# FRONT-UNIT-7INCH.net
KiCad netlist of a schematic drawn in Altium Designer
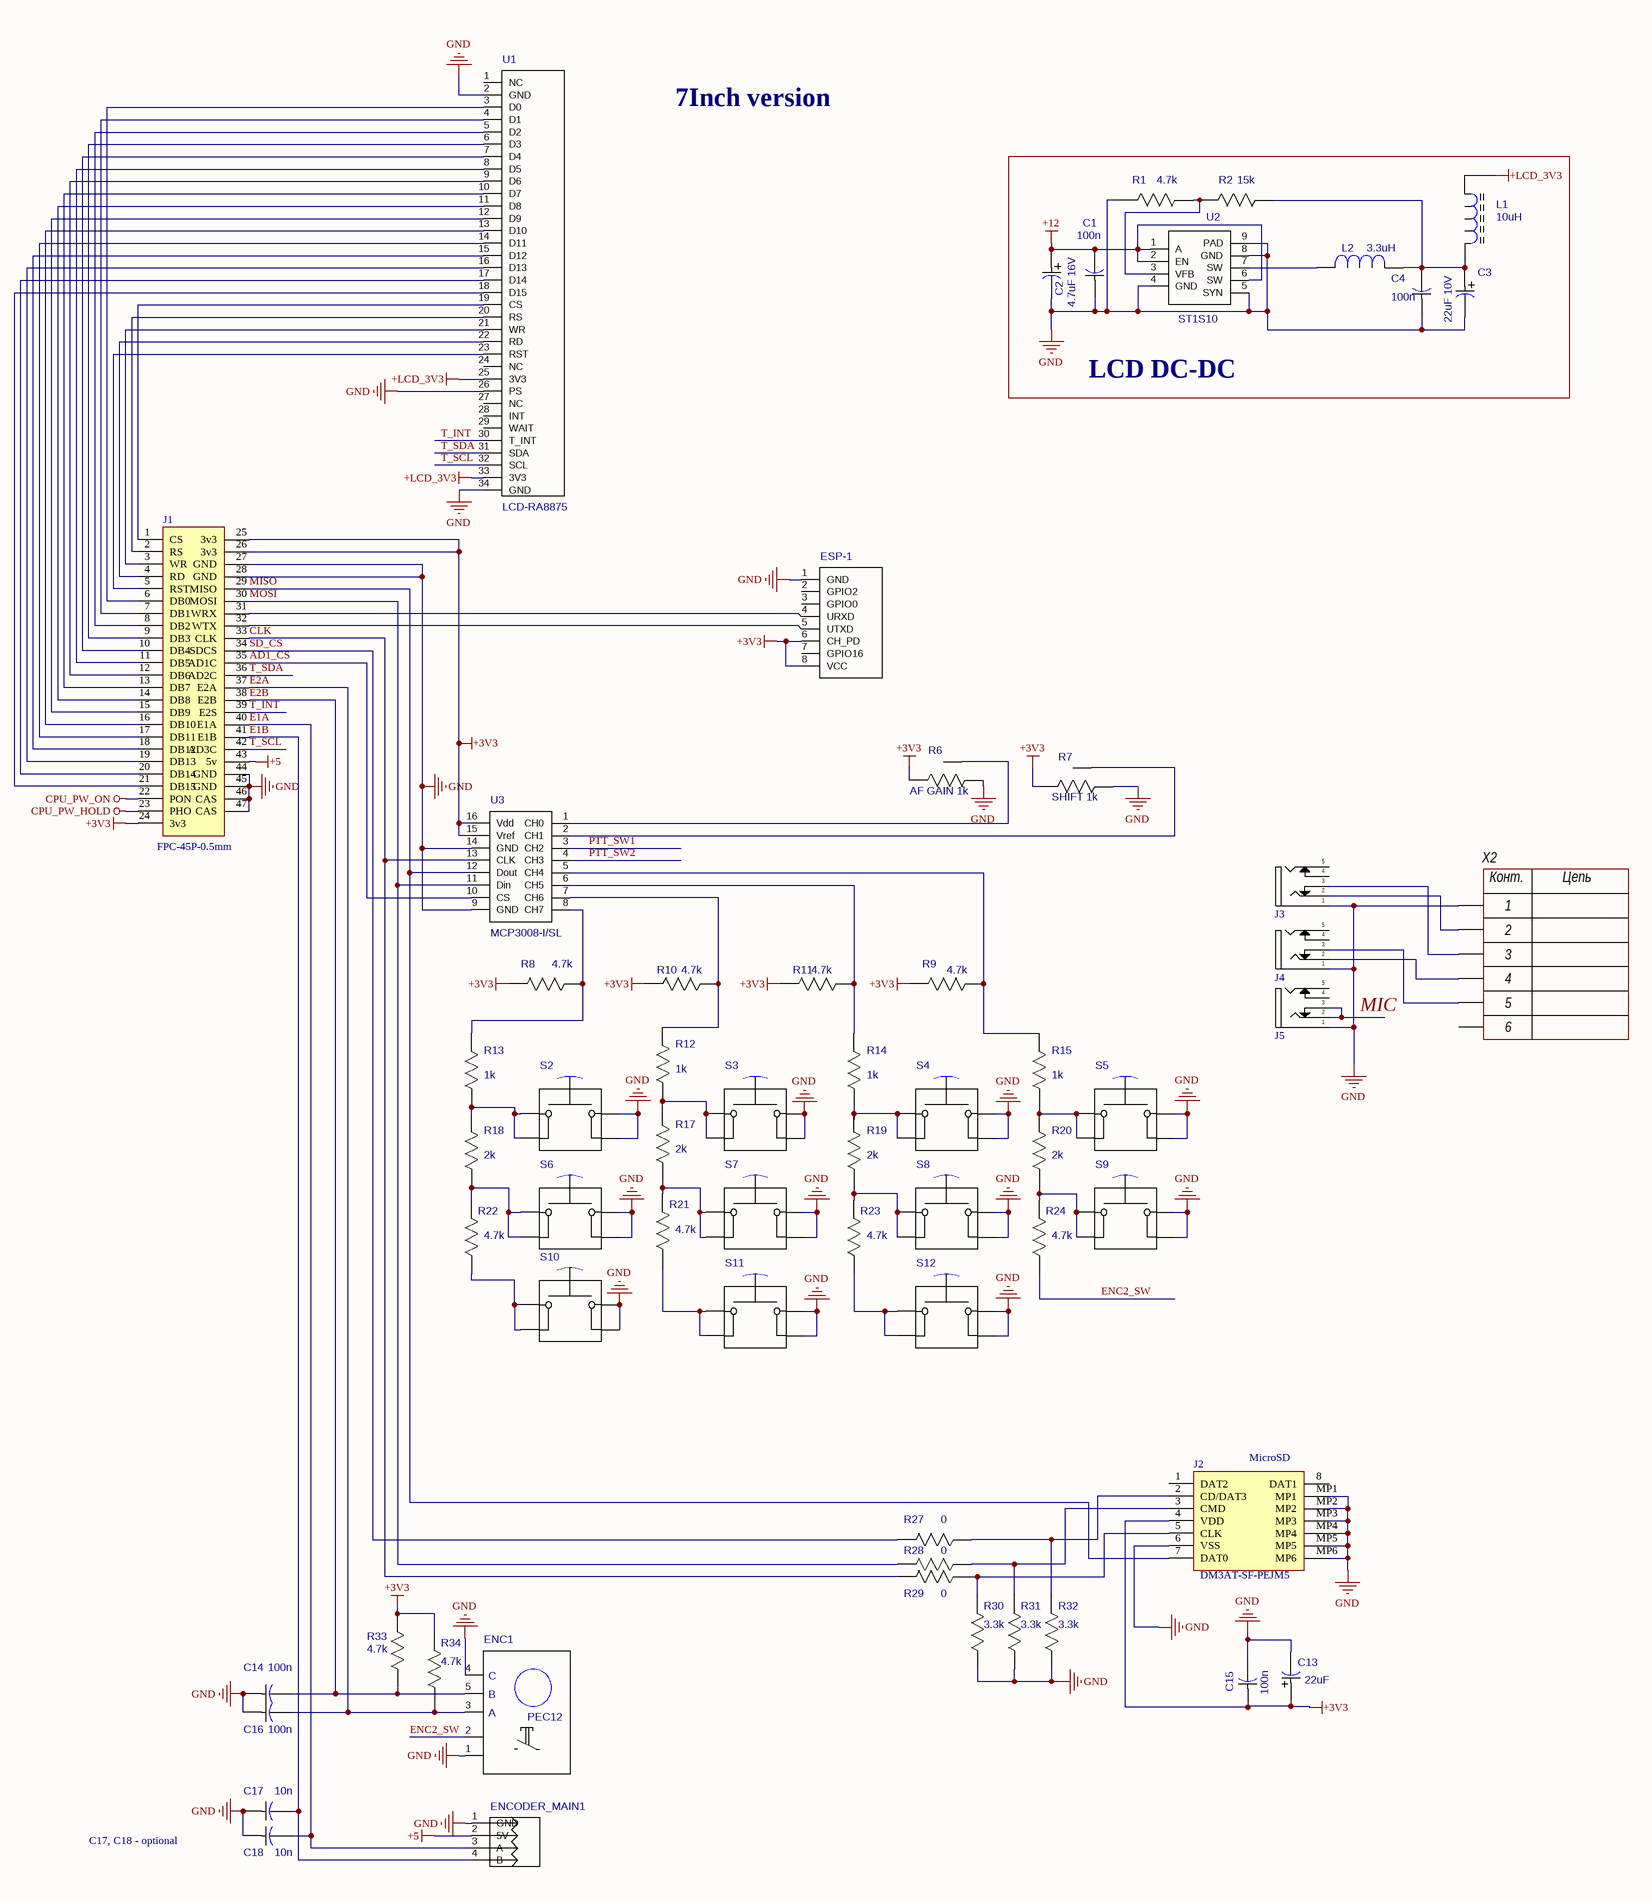
[diagram p0: FRONT-UNIT-7INCH.SCHDOC, left]
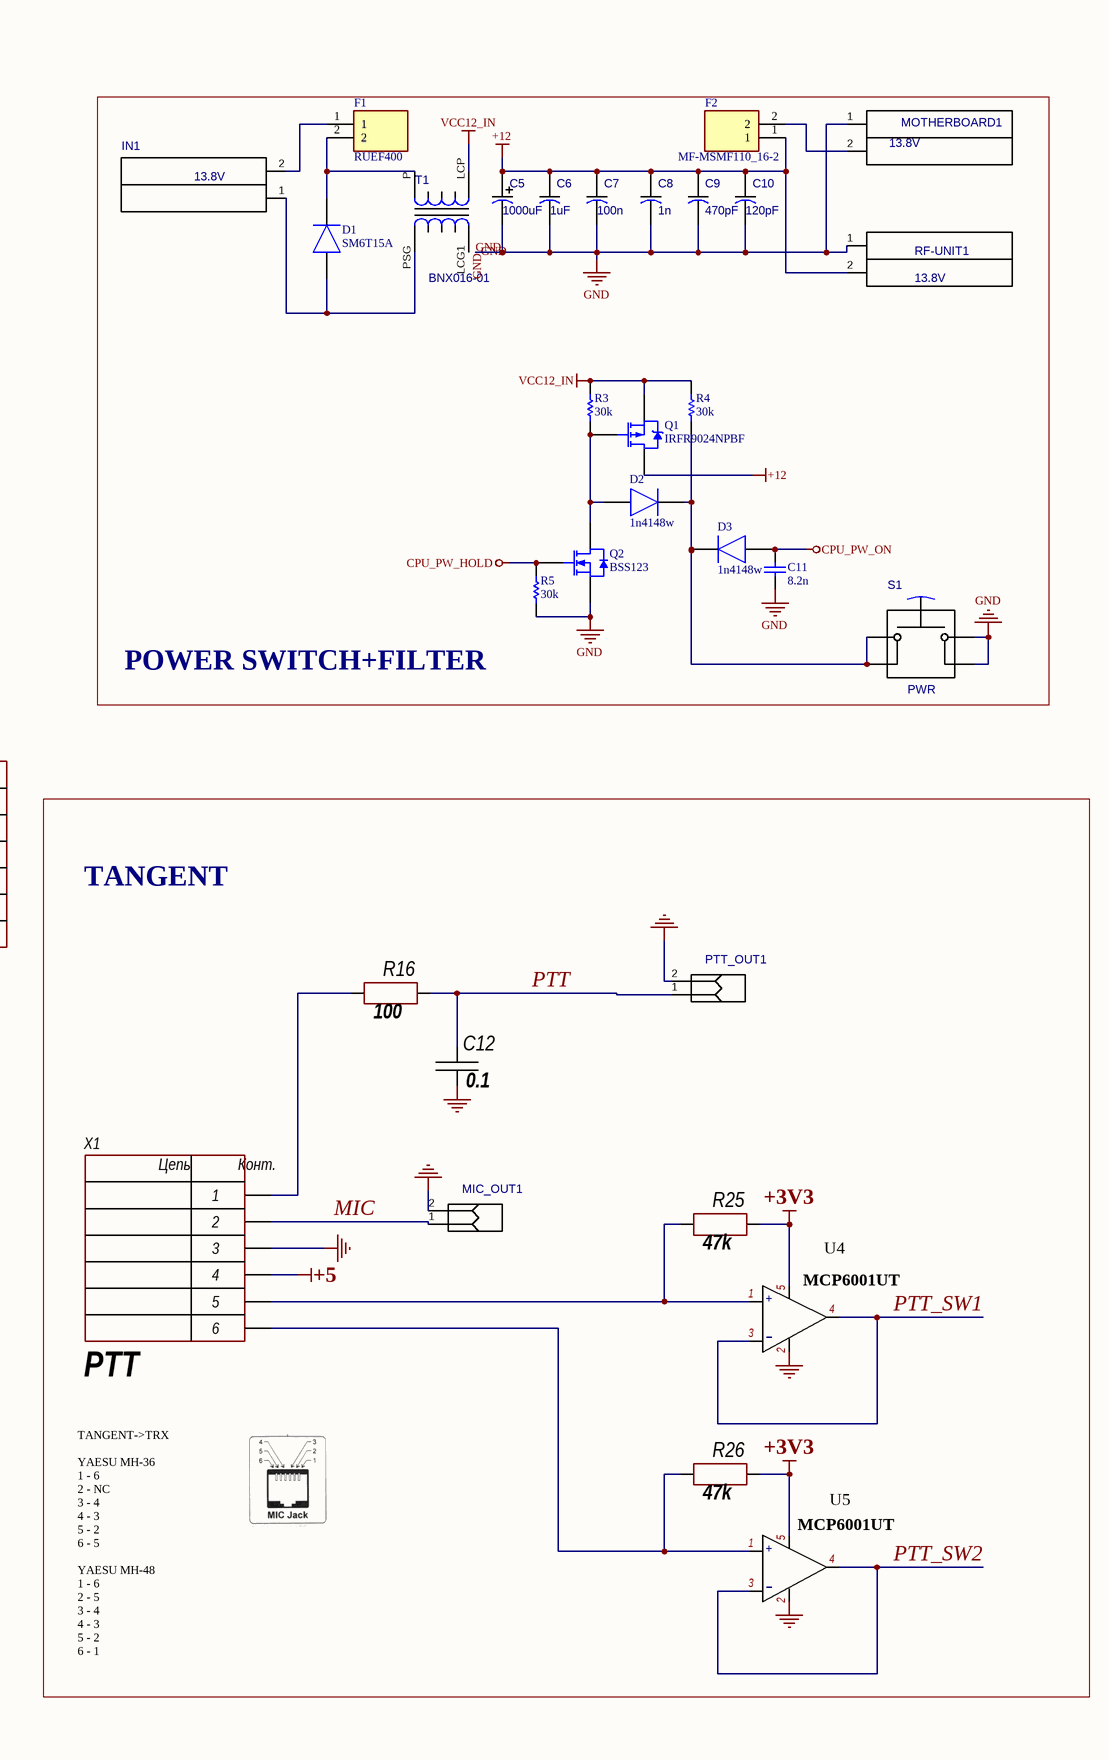
[diagram p1: FRONT-UNIT-7INCH.SCHDOC, right]

(export (version "E")
  (design (tool "Eeschema 10.0.6"))
  (components
    (comp (ref "C1")
      (value "100n")
      (footprint "CAP_0805")
      (description "CAP_0805")
      (libsource (lib "*") (part "CAP_0805"))
    )
    (comp (ref "C2")
      (value "4.7uF 16V")
      (footprint "CAPAE-6.6x6.6h5.4")
      (description "CAPAE_6.6x6.6h5.4")
      (libsource (lib "*") (part "CAPAE_6.6x6.6h5.4"))
    )
    (comp (ref "C3")
      (value "22uF 10V")
      (footprint "TC_1411")
      (description "CAPAE_4.3x4.3h5.4")
      (libsource (lib "*") (part "CAPAE_4.3x4.3h5.4"))
    )
    (comp (ref "C4")
      (value "100n")
      (footprint "CAP_0805")
      (description "CAP_0805")
      (libsource (lib "FRONT-UNIT-7INCH") (part "CAP_0805"))
    )
    (comp (ref "C5")
      (value "1000uF")
      (footprint "CAPPR-6.35/8.9")
      (description "CAP250RP")
      (libsource (lib "*") (part "CAP250RP"))
    )
    (comp (ref "C6")
      (value "1uF")
      (footprint "CAP_1206")
      (description "CAP_1206")
      (libsource (lib "*") (part "CAP_1206"))
    )
    (comp (ref "C7")
      (value "100n")
      (footprint "CAP_1206")
      (description "CAP_1206")
      (libsource (lib "*") (part "CAP_1206"))
    )
    (comp (ref "C8")
      (value "1n")
      (footprint "CAP_1206")
      (description "CAP_1206")
      (libsource (lib "*") (part "CAP_1206"))
    )
    (comp (ref "C9")
      (value "470pF")
      (footprint "CAP_1206")
      (description "CAP_1206")
      (libsource (lib "*") (part "CAP_1206"))
    )
    (comp (ref "C10")
      (value "120pF")
      (footprint "CAP_1206")
      (description "CAP_1206")
      (libsource (lib "FRONT-UNIT-7INCH") (part "CAP_1206"))
    )
    (comp (ref "C11")
      (value "8.2n")
      (footprint "CAPC2013X94X50LL20T25")
      (description "CAP_1206")
      (fields
        (field (name "MANUFACTURER") "AVX Interconnect / Elco")
        (field (name "PART NUMBER") "08055C822KAT2A")
      )
      (libsource (lib "Altium Content Vault") (part "CAP"))
    )
    (comp (ref "C12")
      (value "0.1")
      (footprint "CH0805C")
      (libsource (lib "FRONT-UNIT-7INCH") (part "Capacitor"))
    )
    (comp (ref "C13")
      (value "22uF")
      (footprint "TC_1411")
      (description "EEEFC_sizeB")
      (libsource (lib "*") (part "EEEFC_sizeB"))
    )
    (comp (ref "C14")
      (value "100n")
      (footprint "CAP_0805")
      (description "CAP_0805")
      (libsource (lib "*") (part "CAP_0805"))
    )
    (comp (ref "C15")
      (value "100n")
      (footprint "CAP_0805")
      (description "CAP_0805")
      (libsource (lib "*") (part "CAP_0805"))
    )
    (comp (ref "C16")
      (value "100n")
      (footprint "CAP_0805")
      (description "CAP_0805")
      (libsource (lib "*") (part "CAP_0805"))
    )
    (comp (ref "C17")
      (value "10n")
      (footprint "CAP_0805")
      (description "CAP_0805")
      (libsource (lib "*") (part "CAP_0805"))
    )
    (comp (ref "C18")
      (value "10n")
      (footprint "CAP_0805")
      (description "CAP_0805")
      (libsource (lib "*") (part "CAP_0805"))
    )
    (comp (ref "D1")
      (value "SM6T15A")
      (footprint "SamacSys:SMBJ36CATR")
      (description "Diode")
      (fields (field (name "MOUSER PART NUMBER") "511-SM6T15A") (field (name "RS PART NUMBER") "4864915P"))
      (libsource (lib "*") (part "SM6T15A"))
    )
    (comp (ref "D2")
      (value "1n4148w")
      (footprint "SamacSys:SOD3716X135N")
      (description "Diode")
      (libsource (lib "*") (part "1n4148w"))
    )
    (comp (ref "D3")
      (value "1n4148w")
      (footprint "SamacSys:SOD3716X135N")
      (description "Diode")
      (libsource (lib "*") (part "1n4148w"))
    )
    (comp (ref "ENC1") (value "PEC12") (footprint "PEC12") (libsource (lib "*") (part "PEC12")))
    (comp (ref "ENCODER_MAIN1")
      (value "OPTICAL ENCODER")
      (footprint "644456-4")
      (libsource (lib "*") (part "644456-4"))
    )
    (comp (ref "ESP-1")
      (value "ESP-01 ESP8266")
      (footprint "ESP-01 ESP8266")
      (libsource (lib "*") (part "ESP-01 ESP8266"))
    )
    (comp (ref "F1")
      (value "RUEF400")
      (footprint "SamacSys:RUEF400")
      (description "Fuse")
      (fields (field (name "MOUSER PART NUMBER") "650-RUEF400") (field (name "RS PART NUMBER") "5176837P"))
      (libsource (lib "*") (part "RUEF400"))
    )
    (comp (ref "F2")
      (value "MF-MSMF110_16-2")
      (footprint "SamacSys:FUSC4632X85N")
      (description "Fuse")
      (fields
        (field (name "MANUFACTURER_PART_NUMBER") "MF-MSMF110/16-2")
        (field (name "MOUSER PART NUMBER") "652-MF-MSMF110/16-2")
      )
      (libsource (lib "*") (part "MF-MSMF110_16-2"))
    )
    (comp (ref "IN1")
      (value "13.8V")
      (footprint "JX2")
      (description "JX2")
      (libsource (lib "*") (part "JX2"))
    )
    (comp (ref "J1")
      (value "FPC-45P-0.5mm")
      (footprint "FH12S45S05SH60")
      (description "Connector")
      (fields
        (field (name "MANUFACTURER_PART_NUMBER") "FH12S-45S-0.5SH(55)")
        (field (name "MOUSER PART NUMBER") "798-FH12S-45S-05SH55")
      )
      (libsource (lib "*") (part "FH12S-45S-0.5SH_55_"))
    )
    (comp (ref "J2")
      (value "DM3AT-SF-PEJM5")
      (footprint "SamacSys:DM3ATSFPEJM5")
      (description "Connector")
      (libsource (lib "*") (part "DM3AT-SF-PEJM5"))
    )
    (comp (ref "J3") (value "PJ-3,5") (footprint "Audio-PJ-392") (libsource (lib "SDR_ham") (part "PJ-3,5")))
    (comp (ref "J4") (value "PJ-3,5") (footprint "Audio-PJ-392") (libsource (lib "SDR_ham") (part "PJ-3,5")))
    (comp (ref "J5") (value "PJ-3,5") (footprint "Audio-PJ-392") (libsource (lib "SDR_ham") (part "PJ-3,5")))
    (comp (ref "L1")
      (value "10uH")
      (footprint "B82464Z4")
      (description "Inductor")
      (libsource (lib "FRONT-UNIT-7INCH") (part "IND_FERRITE_CORE"))
    )
    (comp (ref "L2")
      (value "3.3uH")
      (footprint "IND_1812")
      (description "IND_1812")
      (libsource (lib "*") (part "IND_1812"))
    )
    (comp (ref "MIC_OUT1")
      (value "MIC_OUT")
      (footprint "51022-0200")
      (description "51022-0200")
      (libsource (lib "*") (part "51022-0200"))
    )
    (comp (ref "MOTHERBOARD1")
      (value "13.8V")
      (footprint "JX2")
      (description "JX2")
      (libsource (lib "*") (part "JX2"))
    )
    (comp (ref "PTT_OUT1")
      (value "PTT_OUT")
      (footprint "51022-0200")
      (description "51022-0200")
      (libsource (lib "*") (part "51022-0200"))
    )
    (comp (ref "Q1")
      (value "IRFR9024NPBF")
      (footprint "ONSC-DPAK-3-369C-01_V")
      (description "IRFR9024NPBF, Транзистор, Р-канал 55В 11А")
      (fields (field (name "MANUFACTURER") "On Semiconductor") (field (name "PARTNUMBER") "NTD2955G"))
      (libsource (lib "Altium Content Vault") (part "ONSC-PMOS-G1S3D4-3_B"))
    )
    (comp (ref "Q2")
      (value "BSS123")
      (footprint "FAIR-SOT23-3_V")
      (fields (field (name "MANUFACTURER") "Fairchild"))
      (libsource (lib "Altium Content Vault") (part "NEMOS-GSD-3"))
    )
    (comp (ref "R1")
      (value "4.7k")
      (footprint "RES_0805")
      (description "RES_0805")
      (libsource (lib "") (part "RES_0805_1"))
    )
    (comp (ref "R2")
      (value "15k")
      (footprint "RES_0805")
      (description "RES_0805")
      (fields (field (name "Comment") "120k+100k"))
      (libsource (lib "") (part "RES_0805_1"))
    )
    (comp (ref "R3")
      (value "30k")
      (footprint "RESC2013X60X40NL20T25")
      (description "RES_0805")
      (fields (field (name "MANUFACTURER") "Panasonic") (field (name "PART NUMBER") "ERA-6AEB303V"))
      (libsource (lib "Altium Content Vault") (part "RES"))
    )
    (comp (ref "R4")
      (value "30k")
      (footprint "RESC2013X60X40NL20T25")
      (description "RES_0805")
      (fields (field (name "MANUFACTURER") "Panasonic") (field (name "PART NUMBER") "ERA-6AEB303V"))
      (libsource (lib "Altium Content Vault") (part "RES"))
    )
    (comp (ref "R5")
      (value "30k")
      (footprint "RESC2013X60X40NL20T25")
      (description "RES_0805")
      (fields (field (name "MANUFACTURER") "Panasonic") (field (name "PART NUMBER") "ERA-6AEB303V"))
      (libsource (lib "Altium Content Vault") (part "RES"))
    )
    (comp (ref "R6")
      (value "AF GAIN 1k")
      (footprint "PTV09")
      (description "Adjustable Resistor PTV09")
      (fields (field (name "Comment") "ptv09a-4225f-b102"))
      (libsource (lib "*") (part "PTV09"))
    )
    (comp (ref "R7")
      (value "SHIFT 1k")
      (footprint "PTV09")
      (description "Adjustable Resistor PTV09")
      (fields (field (name "Comment") "ptv09a-4225f-b102"))
      (libsource (lib "*") (part "PTV09"))
    )
    (comp (ref "R8")
      (value "4.7k")
      (footprint "RES_0805")
      (description "RES_0805")
      (libsource (lib "*") (part "RES_0805"))
    )
    (comp (ref "R9")
      (value "4.7k")
      (footprint "RES_0805")
      (description "RES_0805")
      (libsource (lib "*") (part "RES_0805"))
    )
    (comp (ref "R10")
      (value "4.7k")
      (footprint "RES_0805")
      (description "RES_0805")
      (libsource (lib "*") (part "RES_0805"))
    )
    (comp (ref "R11")
      (value "4.7k")
      (footprint "RES_0805")
      (description "RES_0805")
      (libsource (lib "*") (part "RES_0805"))
    )
    (comp (ref "R12")
      (value "1k")
      (footprint "RES_0805")
      (description "RES_0805")
      (libsource (lib "*") (part "RES_0805"))
    )
    (comp (ref "R13")
      (value "1k")
      (footprint "RES_0805")
      (description "RES_0805")
      (libsource (lib "*") (part "RES_0805"))
    )
    (comp (ref "R14")
      (value "1k")
      (footprint "RES_0805")
      (description "RES_0805")
      (libsource (lib "*") (part "RES_0805"))
    )
    (comp (ref "R15")
      (value "1k")
      (footprint "RES_0805")
      (description "RES_0805")
      (libsource (lib "*") (part "RES_0805"))
    )
    (comp (ref "R16")
      (value "100")
      (footprint "FRONT-UNIT-7INCH:CH0805R")
      (libsource (lib "Discrete") (part "Resistor"))
    )
    (comp (ref "R17")
      (value "2k")
      (footprint "RES_0805")
      (description "RES_0805")
      (libsource (lib "*") (part "RES_0805"))
    )
    (comp (ref "R18")
      (value "2k")
      (footprint "RES_0805")
      (description "RES_0805")
      (libsource (lib "*") (part "RES_0805"))
    )
    (comp (ref "R19")
      (value "2k")
      (footprint "RES_0805")
      (description "RES_0805")
      (libsource (lib "*") (part "RES_0805"))
    )
    (comp (ref "R20")
      (value "2k")
      (footprint "RES_0805")
      (description "RES_0805")
      (libsource (lib "*") (part "RES_0805"))
    )
    (comp (ref "R21")
      (value "4.7k")
      (footprint "RES_0805")
      (description "RES_0805")
      (libsource (lib "*") (part "RES_0805"))
    )
    (comp (ref "R22")
      (value "4.7k")
      (footprint "RES_0805")
      (description "RES_0805")
      (libsource (lib "*") (part "RES_0805"))
    )
    (comp (ref "R23")
      (value "4.7k")
      (footprint "RES_0805")
      (description "RES_0805")
      (libsource (lib "*") (part "RES_0805"))
    )
    (comp (ref "R24")
      (value "4.7k")
      (footprint "RES_0805")
      (description "RES_0805")
      (libsource (lib "*") (part "RES_0805"))
    )
    (comp (ref "R25")
      (value "47k")
      (footprint "FRONT-UNIT-7INCH:CH0805R")
      (libsource (lib "Discrete") (part "Resistor"))
    )
    (comp (ref "R26")
      (value "47k")
      (footprint "FRONT-UNIT-7INCH:CH0805C")
      (libsource (lib "Discrete") (part "Resistor"))
    )
    (comp (ref "R27")
      (value "0")
      (footprint "RES_0805")
      (description "RES_0805")
      (libsource (lib "*") (part "RES_0805"))
    )
    (comp (ref "R28")
      (value "0")
      (footprint "RES_0805")
      (description "RES_0805")
      (libsource (lib "*") (part "RES_0805"))
    )
    (comp (ref "R29")
      (value "0")
      (footprint "RES_0805")
      (description "RES_0805")
      (libsource (lib "*") (part "RES_0805"))
    )
    (comp (ref "R30")
      (value "3.3k")
      (footprint "RES_0805")
      (description "RES_0805")
      (libsource (lib "*") (part "RES_0805"))
    )
    (comp (ref "R31")
      (value "3.3k")
      (footprint "RES_0805")
      (description "RES_0805")
      (libsource (lib "*") (part "RES_0805"))
    )
    (comp (ref "R32")
      (value "3.3k")
      (footprint "RES_0805")
      (description "RES_0805")
      (libsource (lib "*") (part "RES_0805"))
    )
    (comp (ref "R33")
      (value "4.7k")
      (footprint "RES_0805")
      (description "RES_0805")
      (libsource (lib "*") (part "RES_0805"))
    )
    (comp (ref "R34")
      (value "4.7k")
      (footprint "RES_0805")
      (description "RES_0805")
      (libsource (lib "*") (part "RES_0805"))
    )
    (comp (ref "RF-UNIT1")
      (value "13.8V")
      (footprint "JX2")
      (description "JX2")
      (libsource (lib "*") (part "JX2"))
    )
    (comp (ref "S1")
      (value "PWR")
      (footprint "PTS-6-S")
      (description "PTS645SK50LFS")
      (libsource (lib "*") (part "PTS645SK50LFS"))
    )
    (comp (ref "S2")
      (value "PTS645SK50LFS")
      (footprint "PTS-6-S")
      (fields (field (name "LCSC PART #") "test"))
      (libsource (lib "*") (part "PTS645SK50LFS"))
    )
    (comp (ref "S3")
      (value "PTS645SK50LFS")
      (footprint "PTS-6-S")
      (libsource (lib "*") (part "PTS645SK50LFS"))
    )
    (comp (ref "S4")
      (value "PTS645SK50LFS")
      (footprint "PTS-6-S")
      (libsource (lib "*") (part "PTS645SK50LFS"))
    )
    (comp (ref "S5")
      (value "PTS645SK50LFS")
      (footprint "PTS-6-S")
      (libsource (lib "*") (part "PTS645SK50LFS"))
    )
    (comp (ref "S6")
      (value "PTS645SK50LFS")
      (footprint "PTS-6-S")
      (libsource (lib "*") (part "PTS645SK50LFS"))
    )
    (comp (ref "S7")
      (value "PTS645SK50LFS")
      (footprint "PTS-6-S")
      (libsource (lib "*") (part "PTS645SK50LFS"))
    )
    (comp (ref "S8")
      (value "PTS645SK50LFS")
      (footprint "PTS-6-S")
      (libsource (lib "*") (part "PTS645SK50LFS"))
    )
    (comp (ref "S9")
      (value "PTS645SK50LFS")
      (footprint "PTS-6-S")
      (libsource (lib "*") (part "PTS645SK50LFS"))
    )
    (comp (ref "S10")
      (value "PTS645SK50LFS")
      (footprint "PTS-6-S")
      (libsource (lib "*") (part "PTS645SK50LFS"))
    )
    (comp (ref "S11")
      (value "PTS645SK50LFS")
      (footprint "PTS-6-S")
      (libsource (lib "*") (part "PTS645SK50LFS"))
    )
    (comp (ref "S12")
      (value "PTS645SK50LFS")
      (footprint "PTS-6-S")
      (libsource (lib "*") (part "PTS645SK50LFS"))
    )
    (comp (ref "T1")
      (value "BNX016-01")
      (footprint "TRANSF_ICORE")
      (libsource (lib "*") (part "TRANSF_ICORE"))
    )
    (comp (ref "U1")
      (value "LCD-RA8875")
      (footprint "LCD-RA8875")
      (libsource (lib "FRONT-UNIT-7INCH") (part "LCD-RA8875"))
    )
    (comp (ref "U2") (value "ST1S10") (footprint "ST1S10") (libsource (lib "*") (part "ST1S10")))
    (comp (ref "U3")
      (value "MCP3008-I/SL")
      (footprint "MCP3008-I/SL")
      (libsource (lib "*") (part "MCP3008-I/SL"))
    )
    (comp (ref "U4")
      (value "MCP6001UT")
      (footprint "SOT23-5")
      (libsource (lib "Analog") (part "MCP6001UT_1"))
    )
    (comp (ref "U5")
      (value "MCP6001UT")
      (footprint "SOT23-5")
      (libsource (lib "Analog") (part "MCP6001UT_1"))
    )
    (comp (ref "X1")
      (value "PTT")
      (footprint "custom:CON: PLS-6")
      (libsource (lib "") (part "6-Connector_1"))
    )
    (comp (ref "X2")
      (value "PTT")
      (footprint "custom:CON: PLS-6")
      (libsource (lib "Connectors") (part "6-Connector"))
    )
  )
  (nets
    (net (code "1") (name "+3V3") (class "Default")
      (node (ref "C13") (pin "1") (pinfunction "PLUS_1") (pintype "passive"))
      (node (ref "C15") (pin "1") (pinfunction "1_1") (pintype "passive"))
      (node (ref "ESP-1") (pin "6") (pinfunction "CH_PD_6") (pintype "passive"))
      (node (ref "ESP-1") (pin "8") (pinfunction "VCC_8") (pintype "passive"))
      (node (ref "J1") (pin "24") (pinfunction "3v3_24") (pintype "passive"))
      (node (ref "J1") (pin "25") (pinfunction "3v3_25") (pintype "passive"))
      (node (ref "J1") (pin "26") (pinfunction "3v3_26") (pintype "passive"))
      (node (ref "J2") (pin "4") (pinfunction "VDD_4") (pintype "passive"))
      (node (ref "R10") (pin "2") (pinfunction "2_2") (pintype "passive"))
      (node (ref "R11") (pin "2") (pinfunction "2_2") (pintype "passive"))
      (node (ref "R25") (pin "2") (pinfunction "2_2") (pintype "passive"))
      (node (ref "R26") (pin "2") (pinfunction "2_2") (pintype "passive"))
      (node (ref "R33") (pin "2") (pinfunction "2_2") (pintype "passive"))
      (node (ref "R34") (pin "2") (pinfunction "2_2") (pintype "passive"))
      (node (ref "R6") (pin "1") (pinfunction "CW_1") (pintype "passive"))
      (node (ref "R7") (pin "1") (pinfunction "CW_1") (pintype "passive"))
      (node (ref "R8") (pin "2") (pinfunction "2_2") (pintype "passive"))
      (node (ref "R9") (pin "2") (pinfunction "2_2") (pintype "passive"))
      (node (ref "U3") (pin "15") (pinfunction "Vref_15") (pintype "passive"))
      (node (ref "U3") (pin "16") (pinfunction "Vdd_16") (pintype "passive"))
      (node (ref "U4") (pin "5") (pinfunction "5_5") (pintype "passive"))
      (node (ref "U5") (pin "5") (pinfunction "5_5") (pintype "passive"))
    )
    (net (code "2") (name "+5") (class "Default")
      (node (ref "ENCODER_MAIN1") (pin "2") (pinfunction "5V_2") (pintype "passive"))
      (node (ref "J1") (pin "43") (pinfunction "5v_43") (pintype "passive"))
      (node (ref "X1") (pin "4") (pinfunction "4_4") (pintype "power_in"))
    )
    (net (code "3") (name "+12") (class "Default")
      (node (ref "C1") (pin "2") (pinfunction "2_2") (pintype "passive"))
      (node (ref "C10") (pin "1") (pinfunction "1_1") (pintype "passive"))
      (node (ref "C2") (pin "1") (pinfunction "PLUS_1") (pintype "passive"))
      (node (ref "C5") (pin "1") (pinfunction "PLUS_1") (pintype "passive"))
      (node (ref "C6") (pin "1") (pinfunction "1_1") (pintype "passive"))
      (node (ref "C7") (pin "1") (pinfunction "1_1") (pintype "passive"))
      (node (ref "C8") (pin "1") (pinfunction "1_1") (pintype "passive"))
      (node (ref "C9") (pin "1") (pinfunction "1_1") (pintype "passive"))
      (node (ref "F2") (pin "1") (pinfunction "1_1") (pintype "passive"))
      (node (ref "Q1") (pin "4") (pinfunction "D_4") (pintype "passive"))
      (node (ref "RF-UNIT1") (pin "2") (pinfunction "1_2") (pintype "passive"))
      (node (ref "U2") (pin "1") (pinfunction "A_1") (pintype "passive"))
      (node (ref "U2") (pin "2") (pinfunction "EN_2") (pintype "passive"))
      (node (ref "U2") (pin "6") (pinfunction "SW_6") (pintype "passive"))
    )
    (net (code "4") (name "+LCD_3V3") (class "Default")
      (node (ref "L1") (pin "1") (pinfunction "A_1") (pintype "passive"))
      (node (ref "U1") (pin "25") (pinfunction "3V3_25") (pintype "passive"))
      (node (ref "U1") (pin "33") (pinfunction "3V3_33") (pintype "passive"))
    )
    (net (code "5") (name "/AD1_CS") (class "Default")
      (node (ref "J1") (pin "35") (pinfunction "AD1C_35") (pintype "passive"))
      (node (ref "U3") (pin "10") (pinfunction "CS_10") (pintype "passive"))
    )
    (net (code "6") (name "/CLK") (class "Default")
      (node (ref "J1") (pin "33") (pinfunction "CLK_33") (pintype "passive"))
      (node (ref "R29") (pin "2") (pinfunction "2_2") (pintype "passive"))
      (node (ref "U3") (pin "13") (pinfunction "CLK_13") (pintype "passive"))
    )
    (net (code "7") (name "/E1A") (class "Default")
      (node (ref "C18") (pin "2") (pinfunction "2_2") (pintype "passive"))
      (node (ref "ENCODER_MAIN1") (pin "3") (pinfunction "A_3") (pintype "passive"))
      (node (ref "J1") (pin "40") (pinfunction "E1A_40") (pintype "passive"))
    )
    (net (code "8") (name "/E1B") (class "Default")
      (node (ref "C17") (pin "2") (pinfunction "2_2") (pintype "passive"))
      (node (ref "ENCODER_MAIN1") (pin "4") (pinfunction "B_4") (pintype "passive"))
      (node (ref "J1") (pin "41") (pinfunction "E1B_41") (pintype "passive"))
    )
    (net (code "9") (name "/E2A") (class "Default")
      (node (ref "C16") (pin "2") (pinfunction "2_2") (pintype "passive"))
      (node (ref "ENC1") (pin "3") (pinfunction "A_3") (pintype "passive"))
      (node (ref "J1") (pin "37") (pinfunction "E2A_37") (pintype "passive"))
      (node (ref "R34") (pin "1") (pinfunction "1_1") (pintype "passive"))
    )
    (net (code "10") (name "/E2B") (class "Default")
      (node (ref "C14") (pin "2") (pinfunction "2_2") (pintype "passive"))
      (node (ref "ENC1") (pin "5") (pinfunction "B_5") (pintype "passive"))
      (node (ref "J1") (pin "38") (pinfunction "E2B_38") (pintype "passive"))
      (node (ref "R33") (pin "1") (pinfunction "1_1") (pintype "passive"))
    )
    (net (code "11") (name "/ENC2_SW") (class "Default")
      (node (ref "ENC1") (pin "2") (pinfunction "2_2") (pintype "passive"))
      (node (ref "R24") (pin "1") (pinfunction "1_1") (pintype "passive"))
    )
    (net (code "12") (name "/MIC") (class "Default")
      (node (ref "J5") (pin "2") (pinfunction "7_2") (pintype "passive"))
      (node (ref "J5") (pin "3") (pinfunction "6_3") (pintype "passive"))
      (node (ref "MIC_OUT1") (pin "1") (pinfunction "1_1") (pintype "passive"))
      (node (ref "X1") (pin "2") (pinfunction "2_2") (pintype "passive"))
    )
    (net (code "13") (name "/MISO") (class "Default")
      (node (ref "J1") (pin "29") (pinfunction "MISO_29") (pintype "passive"))
      (node (ref "J2") (pin "7") (pinfunction "DAT0_7") (pintype "passive"))
      (node (ref "U3") (pin "12") (pinfunction "Dout_12") (pintype "passive"))
    )
    (net (code "14") (name "/MOSI") (class "Default")
      (node (ref "J1") (pin "30") (pinfunction "MOSI_30") (pintype "passive"))
      (node (ref "R28") (pin "2") (pinfunction "2_2") (pintype "passive"))
      (node (ref "U3") (pin "11") (pinfunction "Din_11") (pintype "passive"))
    )
    (net (code "15") (name "/PTT") (class "Default")
      (node (ref "C12") (pin "2") (pinfunction "2_2") (pintype "power_in"))
      (node (ref "PTT_OUT1") (pin "1") (pinfunction "1_1") (pintype "passive"))
      (node (ref "R16") (pin "2") (pinfunction "2_2") (pintype "passive"))
    )
    (net (code "16") (name "/PTT_SW1") (class "Default")
      (node (ref "U3") (pin "3") (pinfunction "CH2_3") (pintype "passive"))
      (node (ref "U4") (pin "3") (pinfunction "3_3") (pintype "passive"))
      (node (ref "U4") (pin "4") (pinfunction "4_4") (pintype "passive"))
    )
    (net (code "17") (name "/PTT_SW2") (class "Default")
      (node (ref "U3") (pin "4") (pinfunction "CH3_4") (pintype "passive"))
      (node (ref "U5") (pin "3") (pinfunction "3_3") (pintype "passive"))
      (node (ref "U5") (pin "4") (pinfunction "4_4") (pintype "passive"))
    )
    (net (code "18") (name "/SD_CS") (class "Default")
      (node (ref "J1") (pin "34") (pinfunction "SDCS_34") (pintype "passive"))
      (node (ref "R27") (pin "2") (pinfunction "2_2") (pintype "passive"))
    )
    (net (code "19") (name "/T_INT") (class "Default")
      (node (ref "J1") (pin "39") (pinfunction "E2S_39") (pintype "passive"))
      (node (ref "U1") (pin "30") (pinfunction "T_INT_30") (pintype "passive"))
    )
    (net (code "20") (name "/T_SCL") (class "Default")
      (node (ref "J1") (pin "42") (pinfunction "AD3C_42") (pintype "passive"))
      (node (ref "U1") (pin "32") (pinfunction "SCL_32") (pintype "passive"))
    )
    (net (code "21") (name "/T_SDA") (class "Default")
      (node (ref "J1") (pin "36") (pinfunction "AD2C_36") (pintype "passive"))
      (node (ref "U1") (pin "31") (pinfunction "SDA_31") (pintype "passive"))
    )
    (net (code "22") (name "CPU_PW_HOLD") (class "Default")
      (node (ref "J1") (pin "23") (pinfunction "PHO_23") (pintype "passive"))
      (node (ref "Q2") (pin "1") (pinfunction "G_1") (pintype "passive"))
      (node (ref "R5") (pin "2") (pinfunction "2_2") (pintype "passive"))
    )
    (net (code "23") (name "CPU_PW_ON") (class "Default")
      (node (ref "C11") (pin "2") (pinfunction "2_2") (pintype "passive"))
      (node (ref "D3") (pin "2") (pinfunction "A_2") (pintype "passive"))
      (node (ref "J1") (pin "22") (pinfunction "PON_22") (pintype "passive"))
    )
    (net (code "24") (name "GND") (class "Default")
      (node (ref "C1") (pin "1") (pinfunction "1_1") (pintype "passive"))
      (node (ref "C10") (pin "2") (pinfunction "2_2") (pintype "passive"))
      (node (ref "C11") (pin "1") (pinfunction "1_1") (pintype "passive"))
      (node (ref "C12") (pin "1") (pinfunction "1_1") (pintype "power_in"))
      (node (ref "C13") (pin "2") (pinfunction "MINUS_2") (pintype "passive"))
      (node (ref "C14") (pin "1") (pinfunction "1_1") (pintype "passive"))
      (node (ref "C15") (pin "2") (pinfunction "2_2") (pintype "passive"))
      (node (ref "C16") (pin "1") (pinfunction "1_1") (pintype "passive"))
      (node (ref "C17") (pin "1") (pinfunction "1_1") (pintype "passive"))
      (node (ref "C18") (pin "1") (pinfunction "1_1") (pintype "passive"))
      (node (ref "C2") (pin "2") (pinfunction "MINUS_2") (pintype "passive"))
      (node (ref "C3") (pin "2") (pinfunction "MINUS_2") (pintype "passive"))
      (node (ref "C4") (pin "1") (pinfunction "1_1") (pintype "passive"))
      (node (ref "C5") (pin "2") (pinfunction "MINUS_2") (pintype "passive"))
      (node (ref "C6") (pin "2") (pinfunction "2_2") (pintype "passive"))
      (node (ref "C7") (pin "2") (pinfunction "2_2") (pintype "passive"))
      (node (ref "C8") (pin "2") (pinfunction "2_2") (pintype "passive"))
      (node (ref "C9") (pin "2") (pinfunction "2_2") (pintype "passive"))
      (node (ref "ENC1") (pin "1") (pinfunction "1_1") (pintype "passive"))
      (node (ref "ENC1") (pin "4") (pinfunction "C_4") (pintype "passive"))
      (node (ref "ENCODER_MAIN1") (pin "1") (pinfunction "GND_1") (pintype "passive"))
      (node (ref "ESP-1") (pin "1") (pinfunction "GND_1") (pintype "passive"))
      (node (ref "J1") (pin "27") (pinfunction "GND_27") (pintype "passive"))
      (node (ref "J1") (pin "28") (pinfunction "GND_28") (pintype "passive"))
      (node (ref "J1") (pin "44") (pinfunction "GND_44") (pintype "passive"))
      (node (ref "J1") (pin "45") (pinfunction "GND_45") (pintype "passive"))
      (node (ref "J1") (pin "46") (pinfunction "CAS_46") (pintype "passive"))
      (node (ref "J1") (pin "47") (pinfunction "CAS_47") (pintype "passive"))
      (node (ref "J2") (pin "6") (pinfunction "VSS_6") (pintype "passive"))
      (node (ref "J2") (pin "MP1") (pinfunction "MP1_MP1") (pintype "passive"))
      (node (ref "J2") (pin "MP2") (pinfunction "MP2_MP2") (pintype "passive"))
      (node (ref "J2") (pin "MP3") (pinfunction "MP3_MP3") (pintype "passive"))
      (node (ref "J2") (pin "MP4") (pinfunction "MP4_MP4") (pintype "passive"))
      (node (ref "J2") (pin "MP5") (pinfunction "MP5_MP5") (pintype "passive"))
      (node (ref "J2") (pin "MP6") (pinfunction "MP6_MP6") (pintype "passive"))
      (node (ref "J3") (pin "1") (pinfunction "8_1") (pintype "passive"))
      (node (ref "J4") (pin "1") (pinfunction "8_1") (pintype "passive"))
      (node (ref "J5") (pin "1") (pinfunction "8_1") (pintype "passive"))
      (node (ref "MIC_OUT1") (pin "2") (pinfunction "2_2") (pintype "passive"))
      (node (ref "MOTHERBOARD1") (pin "1") (pinfunction "2_1") (pintype "passive"))
      (node (ref "PTT_OUT1") (pin "2") (pinfunction "2_2") (pintype "passive"))
      (node (ref "Q2") (pin "2") (pinfunction "S_2") (pintype "passive"))
      (node (ref "R1") (pin "1") (pinfunction "1_1") (pintype "passive"))
      (node (ref "R30") (pin "1") (pinfunction "1_1") (pintype "passive"))
      (node (ref "R31") (pin "1") (pinfunction "1_1") (pintype "passive"))
      (node (ref "R32") (pin "1") (pinfunction "1_1") (pintype "passive"))
      (node (ref "R5") (pin "1") (pinfunction "1_1") (pintype "passive"))
      (node (ref "R6") (pin "3") (pinfunction "CCW_3") (pintype "passive"))
      (node (ref "R7") (pin "3") (pinfunction "CCW_3") (pintype "passive"))
      (node (ref "RF-UNIT1") (pin "1") (pinfunction "2_1") (pintype "passive"))
      (node (ref "S1") (pin "3") (pinfunction "B_3") (pintype "passive"))
      (node (ref "S1") (pin "4") (pinfunction "B_4") (pintype "passive"))
      (node (ref "S10") (pin "3") (pinfunction "B_3") (pintype "passive"))
      (node (ref "S10") (pin "4") (pinfunction "B_4") (pintype "passive"))
      (node (ref "S11") (pin "3") (pinfunction "B_3") (pintype "passive"))
      (node (ref "S11") (pin "4") (pinfunction "B_4") (pintype "passive"))
      (node (ref "S12") (pin "3") (pinfunction "B_3") (pintype "passive"))
      (node (ref "S12") (pin "4") (pinfunction "B_4") (pintype "passive"))
      (node (ref "S2") (pin "3") (pinfunction "B_3") (pintype "passive"))
      (node (ref "S2") (pin "4") (pinfunction "B_4") (pintype "passive"))
      (node (ref "S3") (pin "3") (pinfunction "B_3") (pintype "passive"))
      (node (ref "S3") (pin "4") (pinfunction "B_4") (pintype "passive"))
      (node (ref "S4") (pin "3") (pinfunction "B_3") (pintype "passive"))
      (node (ref "S4") (pin "4") (pinfunction "B_4") (pintype "passive"))
      (node (ref "S5") (pin "3") (pinfunction "B_3") (pintype "passive"))
      (node (ref "S5") (pin "4") (pinfunction "B_4") (pintype "passive"))
      (node (ref "S6") (pin "3") (pinfunction "B_3") (pintype "passive"))
      (node (ref "S6") (pin "4") (pinfunction "B_4") (pintype "passive"))
      (node (ref "S7") (pin "3") (pinfunction "B_3") (pintype "passive"))
      (node (ref "S7") (pin "4") (pinfunction "B_4") (pintype "passive"))
      (node (ref "S8") (pin "3") (pinfunction "B_3") (pintype "passive"))
      (node (ref "S8") (pin "4") (pinfunction "B_4") (pintype "passive"))
      (node (ref "S9") (pin "3") (pinfunction "B_3") (pintype "passive"))
      (node (ref "S9") (pin "4") (pinfunction "B_4") (pintype "passive"))
      (node (ref "T1") (pin "LCG1") (pinfunction "S2_LCG1") (pintype "passive"))
      (node (ref "U1") (pin "2") (pinfunction "GND_2") (pintype "passive"))
      (node (ref "U1") (pin "26") (pinfunction "PS_26") (pintype "passive"))
      (node (ref "U1") (pin "34") (pinfunction "GND_34") (pintype "passive"))
      (node (ref "U2") (pin "4") (pinfunction "GND_4") (pintype "passive"))
      (node (ref "U2") (pin "5") (pinfunction "SYN_5") (pintype "passive"))
      (node (ref "U2") (pin "8") (pinfunction "GND_8") (pintype "passive"))
      (node (ref "U2") (pin "9") (pinfunction "PAD_9") (pintype "passive"))
      (node (ref "U3") (pin "14") (pinfunction "GND_14") (pintype "passive"))
      (node (ref "U3") (pin "9") (pinfunction "GND_9") (pintype "passive"))
      (node (ref "U4") (pin "2") (pinfunction "2_2") (pintype "passive"))
      (node (ref "U5") (pin "2") (pinfunction "2_2") (pintype "passive"))
      (node (ref "X1") (pin "3") (pinfunction "3_3") (pintype "power_in"))
      (node (ref "X2") (pin "1") (pinfunction "1_1") (pintype "passive"))
    )
    (net (code "25") (name "Net-(C3-PLUS)") (class "Default")
      (node (ref "C3") (pin "1") (pinfunction "PLUS_1") (pintype "passive"))
      (node (ref "C4") (pin "2") (pinfunction "2_2") (pintype "passive"))
      (node (ref "L1") (pin "2") (pinfunction "B_2") (pintype "passive"))
      (node (ref "L2") (pin "2") (pinfunction "2_2") (pintype "passive"))
      (node (ref "R2") (pin "2") (pinfunction "2_2") (pintype "passive"))
    )
    (net (code "26") (name "Net-(D1-A)") (class "Default")
      (node (ref "D1") (pin "2") (pinfunction "A_2") (pintype "passive"))
      (node (ref "IN1") (pin "1") (pinfunction "2_1") (pintype "passive"))
      (node (ref "T1") (pin "PSG") (pinfunction "S1_PSG") (pintype "passive"))
    )
    (net (code "27") (name "Net-(D1-K)") (class "Default")
      (node (ref "D1") (pin "1") (pinfunction "K_1") (pintype "passive"))
      (node (ref "F1") (pin "2") (pinfunction "2_2") (pintype "passive"))
      (node (ref "T1") (pin "P") (pinfunction "P1_P") (pintype "passive"))
    )
    (net (code "28") (name "Net-(D2-A)") (class "Default")
      (node (ref "D2") (pin "2") (pinfunction "A_2") (pintype "passive"))
      (node (ref "Q1") (pin "1") (pinfunction "G_1") (pintype "passive"))
      (node (ref "Q2") (pin "3") (pinfunction "D_3") (pintype "passive"))
      (node (ref "R3") (pin "1") (pinfunction "1_1") (pintype "passive"))
    )
    (net (code "29") (name "Net-(D2-K)") (class "Default")
      (node (ref "D2") (pin "1") (pinfunction "K_1") (pintype "passive"))
      (node (ref "D3") (pin "1") (pinfunction "K_1") (pintype "passive"))
      (node (ref "R4") (pin "1") (pinfunction "1_1") (pintype "passive"))
      (node (ref "S1") (pin "1") (pinfunction "A_1") (pintype "passive"))
      (node (ref "S1") (pin "2") (pinfunction "A_2") (pintype "passive"))
    )
    (net (code "30") (name "Net-(ESP-1-URXD)") (class "Default")
      (node (ref "ESP-1") (pin "4") (pinfunction "URXD_4") (pintype "passive"))
      (node (ref "J1") (pin "31") (pinfunction "WRX_31") (pintype "passive"))
    )
    (net (code "31") (name "Net-(ESP-1-UTXD)") (class "Default")
      (node (ref "ESP-1") (pin "5") (pinfunction "UTXD_5") (pintype "passive"))
      (node (ref "J1") (pin "32") (pinfunction "WTX_32") (pintype "passive"))
    )
    (net (code "32") (name "Net-(IN1-1)") (class "Default")
      (node (ref "F1") (pin "1") (pinfunction "1_1") (pintype "passive"))
      (node (ref "IN1") (pin "2") (pinfunction "1_2") (pintype "passive"))
    )
    (net (code "33") (name "Net-(J1-CS)") (class "Default")
      (node (ref "J1") (pin "1") (pinfunction "CS_1") (pintype "passive"))
      (node (ref "U1") (pin "19") (pinfunction "CS_19") (pintype "passive"))
    )
    (net (code "34") (name "Net-(J1-DB0)") (class "Default")
      (node (ref "J1") (pin "6") (pinfunction "DB0_6") (pintype "passive"))
      (node (ref "U1") (pin "3") (pinfunction "D0_3") (pintype "passive"))
    )
    (net (code "35") (name "Net-(J1-DB1)") (class "Default")
      (node (ref "J1") (pin "7") (pinfunction "DB1_7") (pintype "passive"))
      (node (ref "U1") (pin "4") (pinfunction "D1_4") (pintype "passive"))
    )
    (net (code "36") (name "Net-(J1-DB2)") (class "Default")
      (node (ref "J1") (pin "8") (pinfunction "DB2_8") (pintype "passive"))
      (node (ref "U1") (pin "5") (pinfunction "D2_5") (pintype "passive"))
    )
    (net (code "37") (name "Net-(J1-DB3)") (class "Default")
      (node (ref "J1") (pin "9") (pinfunction "DB3_9") (pintype "passive"))
      (node (ref "U1") (pin "6") (pinfunction "D3_6") (pintype "passive"))
    )
    (net (code "38") (name "Net-(J1-DB4)") (class "Default")
      (node (ref "J1") (pin "10") (pinfunction "DB4_10") (pintype "passive"))
      (node (ref "U1") (pin "7") (pinfunction "D4_7") (pintype "passive"))
    )
    (net (code "39") (name "Net-(J1-DB5)") (class "Default")
      (node (ref "J1") (pin "11") (pinfunction "DB5_11") (pintype "passive"))
      (node (ref "U1") (pin "8") (pinfunction "D5_8") (pintype "passive"))
    )
    (net (code "40") (name "Net-(J1-DB6)") (class "Default")
      (node (ref "J1") (pin "12") (pinfunction "DB6_12") (pintype "passive"))
      (node (ref "U1") (pin "9") (pinfunction "D6_9") (pintype "passive"))
    )
    (net (code "41") (name "Net-(J1-DB7)") (class "Default")
      (node (ref "J1") (pin "13") (pinfunction "DB7_13") (pintype "passive"))
      (node (ref "U1") (pin "10") (pinfunction "D7_10") (pintype "passive"))
    )
    (net (code "42") (name "Net-(J1-DB8)") (class "Default")
      (node (ref "J1") (pin "14") (pinfunction "DB8_14") (pintype "passive"))
      (node (ref "U1") (pin "11") (pinfunction "D8_11") (pintype "passive"))
    )
    (net (code "43") (name "Net-(J1-DB9)") (class "Default")
      (node (ref "J1") (pin "15") (pinfunction "DB9_15") (pintype "passive"))
      (node (ref "U1") (pin "12") (pinfunction "D9_12") (pintype "passive"))
    )
    (net (code "44") (name "Net-(J1-DB10)") (class "Default")
      (node (ref "J1") (pin "16") (pinfunction "DB10_16") (pintype "passive"))
      (node (ref "U1") (pin "13") (pinfunction "D10_13") (pintype "passive"))
    )
    (net (code "45") (name "Net-(J1-DB11)") (class "Default")
      (node (ref "J1") (pin "17") (pinfunction "DB11_17") (pintype "passive"))
      (node (ref "U1") (pin "14") (pinfunction "D11_14") (pintype "passive"))
    )
    (net (code "46") (name "Net-(J1-DB12)") (class "Default")
      (node (ref "J1") (pin "18") (pinfunction "DB12_18") (pintype "passive"))
      (node (ref "U1") (pin "15") (pinfunction "D12_15") (pintype "passive"))
    )
    (net (code "47") (name "Net-(J1-DB13)") (class "Default")
      (node (ref "J1") (pin "19") (pinfunction "DB13_19") (pintype "passive"))
      (node (ref "U1") (pin "16") (pinfunction "D13_16") (pintype "passive"))
    )
    (net (code "48") (name "Net-(J1-DB14)") (class "Default")
      (node (ref "J1") (pin "20") (pinfunction "DB14_20") (pintype "passive"))
      (node (ref "U1") (pin "17") (pinfunction "D14_17") (pintype "passive"))
    )
    (net (code "49") (name "Net-(J1-DB15)") (class "Default")
      (node (ref "J1") (pin "21") (pinfunction "DB15_21") (pintype "passive"))
      (node (ref "U1") (pin "18") (pinfunction "D15_18") (pintype "passive"))
    )
    (net (code "50") (name "Net-(J1-RD)") (class "Default")
      (node (ref "J1") (pin "4") (pinfunction "RD_4") (pintype "passive"))
      (node (ref "U1") (pin "22") (pinfunction "RD_22") (pintype "passive"))
    )
    (net (code "51") (name "Net-(J1-RS)") (class "Default")
      (node (ref "J1") (pin "2") (pinfunction "RS_2") (pintype "passive"))
      (node (ref "U1") (pin "20") (pinfunction "RS_20") (pintype "passive"))
    )
    (net (code "52") (name "Net-(J1-RST)") (class "Default")
      (node (ref "J1") (pin "5") (pinfunction "RST_5") (pintype "passive"))
      (node (ref "U1") (pin "23") (pinfunction "RST_23") (pintype "passive"))
    )
    (net (code "53") (name "Net-(J1-WR)") (class "Default")
      (node (ref "J1") (pin "3") (pinfunction "WR_3") (pintype "passive"))
      (node (ref "U1") (pin "21") (pinfunction "WR_21") (pintype "passive"))
    )
    (net (code "54") (name "Net-(J2-CD{slash}DAT3)") (class "Default")
      (node (ref "J2") (pin "2") (pinfunction "CD/DAT3_2") (pintype "passive"))
      (node (ref "R27") (pin "1") (pinfunction "1_1") (pintype "passive"))
      (node (ref "R32") (pin "2") (pinfunction "2_2") (pintype "passive"))
    )
    (net (code "55") (name "Net-(J2-CLK)") (class "Default")
      (node (ref "J2") (pin "5") (pinfunction "CLK_5") (pintype "passive"))
      (node (ref "R29") (pin "1") (pinfunction "1_1") (pintype "passive"))
      (node (ref "R30") (pin "2") (pinfunction "2_2") (pintype "passive"))
    )
    (net (code "56") (name "Net-(J2-CMD)") (class "Default")
      (node (ref "J2") (pin "3") (pinfunction "CMD_3") (pintype "passive"))
      (node (ref "R28") (pin "1") (pinfunction "1_1") (pintype "passive"))
      (node (ref "R31") (pin "2") (pinfunction "2_2") (pintype "passive"))
    )
    (net (code "57") (name "Net-(J3-6)") (class "Default")
      (node (ref "J3") (pin "3") (pinfunction "6_3") (pintype "passive"))
      (node (ref "X2") (pin "3") (pinfunction "3_3") (pintype "power_in"))
    )
    (net (code "58") (name "Net-(J3-7)") (class "Default")
      (node (ref "J3") (pin "2") (pinfunction "7_2") (pintype "passive"))
      (node (ref "X2") (pin "2") (pinfunction "2_2") (pintype "passive"))
    )
    (net (code "59") (name "Net-(J4-6)") (class "Default")
      (node (ref "J4") (pin "3") (pinfunction "6_3") (pintype "passive"))
      (node (ref "X2") (pin "5") (pinfunction "5_5") (pintype "power_in"))
    )
    (net (code "60") (name "Net-(J4-7)") (class "Default")
      (node (ref "J4") (pin "2") (pinfunction "7_2") (pintype "passive"))
      (node (ref "X2") (pin "4") (pinfunction "4_4") (pintype "power_in"))
    )
    (net (code "61") (name "Net-(L2-Pad1)") (class "Default")
      (node (ref "L2") (pin "1") (pinfunction "1_1") (pintype "passive"))
      (node (ref "U2") (pin "7") (pinfunction "SW_7") (pintype "passive"))
    )
    (net (code "62") (name "Net-(MOTHERBOARD1-1)") (class "Default")
      (node (ref "F2") (pin "2") (pinfunction "2_2") (pintype "passive"))
      (node (ref "MOTHERBOARD1") (pin "2") (pinfunction "1_2") (pintype "passive"))
    )
    (net (code "63") (name "Net-(R6-W)") (class "Default")
      (node (ref "R6") (pin "2") (pinfunction "W_2") (pintype "passive"))
      (node (ref "U3") (pin "1") (pinfunction "CH0_1") (pintype "passive"))
    )
    (net (code "64") (name "Net-(R7-W)") (class "Default")
      (node (ref "R7") (pin "2") (pinfunction "W_2") (pintype "passive"))
      (node (ref "U3") (pin "2") (pinfunction "CH1_2") (pintype "passive"))
    )
    (net (code "65") (name "Net-(R12-Pad1)") (class "Default")
      (node (ref "R12") (pin "1") (pinfunction "1_1") (pintype "passive"))
      (node (ref "R17") (pin "2") (pinfunction "2_2") (pintype "passive"))
      (node (ref "S3") (pin "1") (pinfunction "A_1") (pintype "passive"))
      (node (ref "S3") (pin "2") (pinfunction "A_2") (pintype "passive"))
    )
    (net (code "66") (name "Net-(R13-Pad1)") (class "Default")
      (node (ref "R13") (pin "1") (pinfunction "1_1") (pintype "passive"))
      (node (ref "R18") (pin "2") (pinfunction "2_2") (pintype "passive"))
      (node (ref "S2") (pin "1") (pinfunction "A_1") (pintype "passive"))
      (node (ref "S2") (pin "2") (pinfunction "A_2") (pintype "passive"))
    )
    (net (code "67") (name "Net-(R14-Pad1)") (class "Default")
      (node (ref "R14") (pin "1") (pinfunction "1_1") (pintype "passive"))
      (node (ref "R19") (pin "2") (pinfunction "2_2") (pintype "passive"))
      (node (ref "S4") (pin "1") (pinfunction "A_1") (pintype "passive"))
      (node (ref "S4") (pin "2") (pinfunction "A_2") (pintype "passive"))
    )
    (net (code "68") (name "Net-(R15-Pad1)") (class "Default")
      (node (ref "R15") (pin "1") (pinfunction "1_1") (pintype "passive"))
      (node (ref "R20") (pin "2") (pinfunction "2_2") (pintype "passive"))
      (node (ref "S5") (pin "1") (pinfunction "A_1") (pintype "passive"))
      (node (ref "S5") (pin "2") (pinfunction "A_2") (pintype "passive"))
    )
    (net (code "69") (name "Net-(R16-Pad1)") (class "Default")
      (node (ref "R16") (pin "1") (pinfunction "1_1") (pintype "passive"))
      (node (ref "X1") (pin "1") (pinfunction "1_1") (pintype "passive"))
    )
    (net (code "70") (name "Net-(R17-Pad1)") (class "Default")
      (node (ref "R17") (pin "1") (pinfunction "1_1") (pintype "passive"))
      (node (ref "R21") (pin "2") (pinfunction "2_2") (pintype "passive"))
      (node (ref "S7") (pin "1") (pinfunction "A_1") (pintype "passive"))
      (node (ref "S7") (pin "2") (pinfunction "A_2") (pintype "passive"))
    )
    (net (code "71") (name "Net-(R18-Pad1)") (class "Default")
      (node (ref "R18") (pin "1") (pinfunction "1_1") (pintype "passive"))
      (node (ref "R22") (pin "2") (pinfunction "2_2") (pintype "passive"))
      (node (ref "S6") (pin "1") (pinfunction "A_1") (pintype "passive"))
      (node (ref "S6") (pin "2") (pinfunction "A_2") (pintype "passive"))
    )
    (net (code "72") (name "Net-(R19-Pad1)") (class "Default")
      (node (ref "R19") (pin "1") (pinfunction "1_1") (pintype "passive"))
      (node (ref "R23") (pin "2") (pinfunction "2_2") (pintype "passive"))
      (node (ref "S8") (pin "1") (pinfunction "A_1") (pintype "passive"))
      (node (ref "S8") (pin "2") (pinfunction "A_2") (pintype "passive"))
    )
    (net (code "73") (name "Net-(R20-Pad1)") (class "Default")
      (node (ref "R20") (pin "1") (pinfunction "1_1") (pintype "passive"))
      (node (ref "R24") (pin "2") (pinfunction "2_2") (pintype "passive"))
      (node (ref "S9") (pin "1") (pinfunction "A_1") (pintype "passive"))
      (node (ref "S9") (pin "2") (pinfunction "A_2") (pintype "passive"))
    )
    (net (code "74") (name "Net-(R21-Pad1)") (class "Default")
      (node (ref "R21") (pin "1") (pinfunction "1_1") (pintype "passive"))
      (node (ref "S11") (pin "1") (pinfunction "A_1") (pintype "passive"))
      (node (ref "S11") (pin "2") (pinfunction "A_2") (pintype "passive"))
    )
    (net (code "75") (name "Net-(R22-Pad1)") (class "Default")
      (node (ref "R22") (pin "1") (pinfunction "1_1") (pintype "passive"))
      (node (ref "S10") (pin "1") (pinfunction "A_1") (pintype "passive"))
      (node (ref "S10") (pin "2") (pinfunction "A_2") (pintype "passive"))
    )
    (net (code "76") (name "Net-(R23-Pad1)") (class "Default")
      (node (ref "R23") (pin "1") (pinfunction "1_1") (pintype "passive"))
      (node (ref "S12") (pin "1") (pinfunction "A_1") (pintype "passive"))
      (node (ref "S12") (pin "2") (pinfunction "A_2") (pintype "passive"))
    )
    (net (code "77") (name "Net-(R25-Pad1)") (class "Default")
      (node (ref "R25") (pin "1") (pinfunction "1_1") (pintype "passive"))
      (node (ref "U4") (pin "1") (pinfunction "1_1") (pintype "passive"))
      (node (ref "X1") (pin "5") (pinfunction "5_5") (pintype "power_in"))
    )
    (net (code "78") (name "Net-(R26-Pad1)") (class "Default")
      (node (ref "R26") (pin "1") (pinfunction "1_1") (pintype "passive"))
      (node (ref "U5") (pin "1") (pinfunction "1_1") (pintype "passive"))
      (node (ref "X1") (pin "6") (pinfunction "6_6") (pintype "power_in"))
    )
    (net (code "79") (name "Net-(U2-VFB)") (class "Default")
      (node (ref "R1") (pin "2") (pinfunction "2_2") (pintype "passive"))
      (node (ref "R2") (pin "1") (pinfunction "1_1") (pintype "passive"))
      (node (ref "U2") (pin "3") (pinfunction "VFB_3") (pintype "passive"))
    )
    (net (code "80") (name "Net-(U3-CH4)") (class "Default")
      (node (ref "R15") (pin "2") (pinfunction "2_2") (pintype "passive"))
      (node (ref "R9") (pin "1") (pinfunction "1_1") (pintype "passive"))
      (node (ref "U3") (pin "5") (pinfunction "CH4_5") (pintype "passive"))
    )
    (net (code "81") (name "Net-(U3-CH5)") (class "Default")
      (node (ref "R11") (pin "1") (pinfunction "1_1") (pintype "passive"))
      (node (ref "R14") (pin "2") (pinfunction "2_2") (pintype "passive"))
      (node (ref "U3") (pin "6") (pinfunction "CH5_6") (pintype "passive"))
    )
    (net (code "82") (name "Net-(U3-CH6)") (class "Default")
      (node (ref "R10") (pin "1") (pinfunction "1_1") (pintype "passive"))
      (node (ref "R12") (pin "2") (pinfunction "2_2") (pintype "passive"))
      (node (ref "U3") (pin "7") (pinfunction "CH6_7") (pintype "passive"))
    )
    (net (code "83") (name "Net-(U3-CH7)") (class "Default")
      (node (ref "R13") (pin "2") (pinfunction "2_2") (pintype "passive"))
      (node (ref "R8") (pin "1") (pinfunction "1_1") (pintype "passive"))
      (node (ref "U3") (pin "8") (pinfunction "CH7_8") (pintype "passive"))
    )
    (net (code "84") (name "VCC12_IN") (class "Default")
      (node (ref "Q1") (pin "3") (pinfunction "S_3") (pintype "passive"))
      (node (ref "R3") (pin "2") (pinfunction "2_2") (pintype "passive"))
      (node (ref "R4") (pin "2") (pinfunction "2_2") (pintype "passive"))
      (node (ref "T1") (pin "LCP") (pinfunction "P2_LCP") (pintype "passive"))
    )
    (net (code "85") (name "unconnected-(ESP-1-GPIO0-Pad3)") (class "Default")
      (node (ref "ESP-1") (pin "3") (pinfunction "GPIO0_3") (pintype "passive"))
    )
    (net (code "86") (name "unconnected-(ESP-1-GPIO2-Pad2)") (class "Default")
      (node (ref "ESP-1") (pin "2") (pinfunction "GPIO2_2") (pintype "passive"))
    )
    (net (code "87") (name "unconnected-(ESP-1-GPIO16-Pad7)") (class "Default")
      (node (ref "ESP-1") (pin "7") (pinfunction "GPIO16_7") (pintype "passive"))
    )
    (net (code "88") (name "unconnected-(J2-DAT1-Pad8)") (class "Default")
      (node (ref "J2") (pin "8") (pinfunction "DAT1_8") (pintype "passive"))
    )
    (net (code "89") (name "unconnected-(J2-DAT2-Pad1)") (class "Default")
      (node (ref "J2") (pin "1") (pinfunction "DAT2_1") (pintype "passive"))
    )
    (net (code "90") (name "unconnected-(J3-4-Pad5)") (class "Default")
      (node (ref "J3") (pin "5") (pinfunction "4_5") (pintype "passive"))
    )
    (net (code "91") (name "unconnected-(J3-5-Pad4)") (class "Default")
      (node (ref "J3") (pin "4") (pinfunction "5_4") (pintype "passive"))
    )
    (net (code "92") (name "unconnected-(J4-4-Pad5)") (class "Default")
      (node (ref "J4") (pin "5") (pinfunction "4_5") (pintype "passive"))
    )
    (net (code "93") (name "unconnected-(J4-5-Pad4)") (class "Default")
      (node (ref "J4") (pin "4") (pinfunction "5_4") (pintype "passive"))
    )
    (net (code "94") (name "unconnected-(J5-4-Pad5)") (class "Default")
      (node (ref "J5") (pin "5") (pinfunction "4_5") (pintype "passive"))
    )
    (net (code "95") (name "unconnected-(J5-5-Pad4)") (class "Default")
      (node (ref "J5") (pin "4") (pinfunction "5_4") (pintype "passive"))
    )
    (net (code "96") (name "unconnected-(U1-INT-Pad28)") (class "Default")
      (node (ref "U1") (pin "28") (pinfunction "INT_28") (pintype "passive"))
    )
    (net (code "97") (name "unconnected-(U1-NC-Pad1)") (class "Default")
      (node (ref "U1") (pin "1") (pinfunction "NC_1") (pintype "passive"))
    )
    (net (code "98") (name "unconnected-(U1-NC-Pad24)") (class "Default")
      (node (ref "U1") (pin "24") (pinfunction "NC_24") (pintype "passive"))
    )
    (net (code "99") (name "unconnected-(U1-NC-Pad27)") (class "Default")
      (node (ref "U1") (pin "27") (pinfunction "NC_27") (pintype "passive"))
    )
    (net (code "100") (name "unconnected-(U1-WAIT-Pad29)") (class "Default")
      (node (ref "U1") (pin "29") (pinfunction "WAIT_29") (pintype "passive"))
    )
    (net (code "101") (name "unconnected-(X2-Pad6)") (class "Default")
      (node (ref "X2") (pin "6") (pinfunction "6_6") (pintype "power_in"))
    )
  )
)
